# Esquem_tico.net
KiCad netlist of a schematic drawn in EAGLE
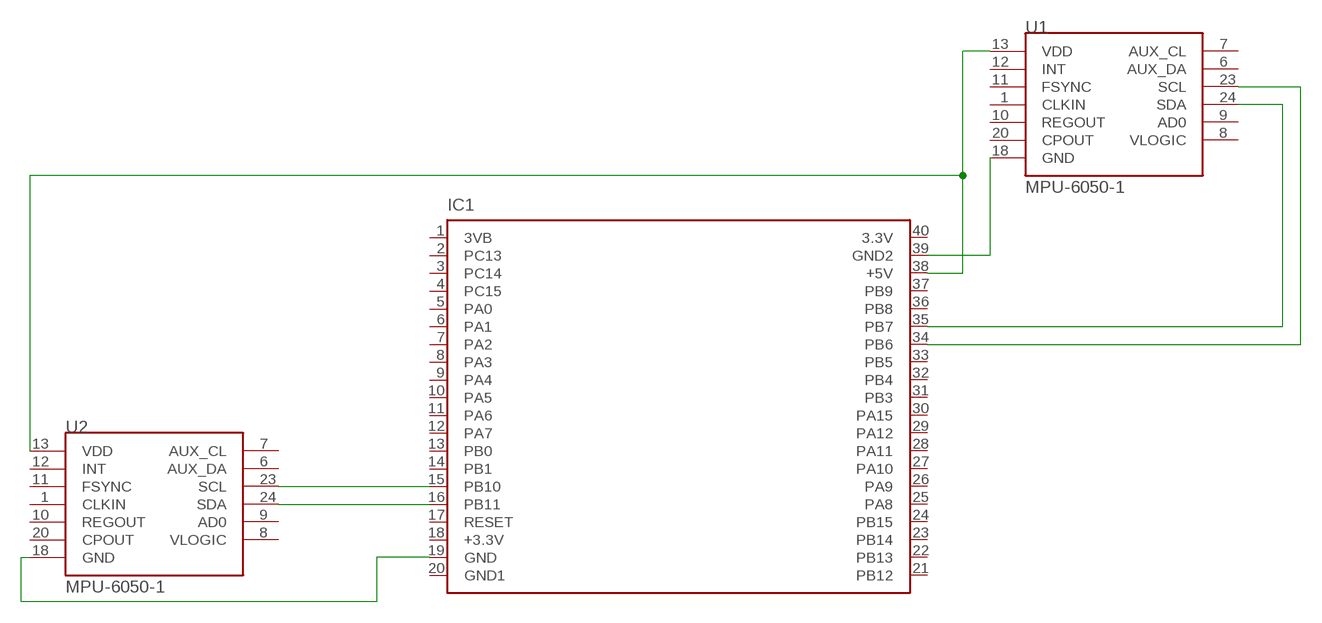
[diagram p0: schematic, sheet 1]

(export (version "E")
  (design (tool "Eeschema 10.0.6"))
  (components
    (comp (ref "IC1")
      (value "BLUEPILL550")
      (footprint "eagle-import:DIL40")
      (fields (field (name "MF") "BluePill"))
      (libsource (lib "eagle-import") (part "BLUEPILL550"))
    )
    (comp (ref "U1")
      (value "MPU-6050-1")
      (footprint "eagle-import:QFN-24-4MM2")
      (libsource (lib "eagle-import") (part "MPU-6050-1"))
    )
    (comp (ref "U2")
      (value "MPU-6050-1")
      (footprint "eagle-import:QFN-24-4MM2")
      (libsource (lib "eagle-import") (part "MPU-6050-1"))
    )
  )
  (nets
    (net (code "1") (name "/PA6") (class "Default")
      (node (ref "IC1") (pin "11") (pinfunction "PA6_11") (pintype "power_in"))
    )
    (net (code "2") (name "/PA7") (class "Default")
      (node (ref "IC1") (pin "12") (pinfunction "PA7_12") (pintype "power_in"))
    )
    (net (code "3") (name "/PB3") (class "Default")
      (node (ref "IC1") (pin "31") (pinfunction "PB3_31") (pintype "power_in"))
    )
    (net (code "4") (name "/PB4") (class "Default")
      (node (ref "IC1") (pin "32") (pinfunction "PB4_32") (pintype "power_in"))
    )
    (net (code "5") (name "Net-(IC1-+5V)") (class "Default")
      (node (ref "IC1") (pin "38") (pinfunction "+5V_38") (pintype "bidirectional"))
      (node (ref "U1") (pin "13") (pinfunction "VDD_13") (pintype "bidirectional"))
      (node (ref "U2") (pin "13") (pinfunction "VDD_13") (pintype "bidirectional"))
    )
    (net (code "6") (name "Net-(IC1-GND)") (class "Default")
      (node (ref "IC1") (pin "19") (pinfunction "GND_19") (pintype "bidirectional"))
      (node (ref "U2") (pin "18") (pinfunction "GND_18") (pintype "bidirectional"))
    )
    (net (code "7") (name "Net-(IC1-GND2)") (class "Default")
      (node (ref "IC1") (pin "39") (pinfunction "GND2_39") (pintype "bidirectional"))
      (node (ref "U1") (pin "18") (pinfunction "GND_18") (pintype "bidirectional"))
    )
    (net (code "8") (name "Net-(IC1-PB6)") (class "Default")
      (node (ref "IC1") (pin "34") (pinfunction "PB6_34") (pintype "bidirectional"))
      (node (ref "U1") (pin "23") (pinfunction "SCL_23") (pintype "bidirectional"))
    )
    (net (code "9") (name "Net-(IC1-PB7)") (class "Default")
      (node (ref "IC1") (pin "35") (pinfunction "PB7_35") (pintype "bidirectional"))
      (node (ref "U1") (pin "24") (pinfunction "SDA_24") (pintype "bidirectional"))
    )
    (net (code "10") (name "Net-(IC1-PB10)") (class "Default")
      (node (ref "IC1") (pin "15") (pinfunction "PB10_15") (pintype "bidirectional"))
      (node (ref "U2") (pin "23") (pinfunction "SCL_23") (pintype "bidirectional"))
    )
    (net (code "11") (name "Net-(IC1-PB11)") (class "Default")
      (node (ref "IC1") (pin "16") (pinfunction "PB11_16") (pintype "bidirectional"))
      (node (ref "U2") (pin "24") (pinfunction "SDA_24") (pintype "bidirectional"))
    )
    (net (code "12") (name "unconnected-(IC1-+3.3V-Pad18)") (class "Default")
      (node (ref "IC1") (pin "18") (pinfunction "+3.3V_18") (pintype "bidirectional"))
    )
    (net (code "13") (name "unconnected-(IC1-3.3V-Pad40)") (class "Default")
      (node (ref "IC1") (pin "40") (pinfunction "3.3V_40") (pintype "bidirectional"))
    )
    (net (code "14") (name "unconnected-(IC1-3VB-Pad1)") (class "Default")
      (node (ref "IC1") (pin "1") (pinfunction "3VB_1") (pintype "input"))
    )
    (net (code "15") (name "unconnected-(IC1-GND1-Pad20)") (class "Default")
      (node (ref "IC1") (pin "20") (pinfunction "GND1_20") (pintype "bidirectional"))
    )
    (net (code "16") (name "unconnected-(IC1-PA0-Pad5)") (class "Default")
      (node (ref "IC1") (pin "5") (pinfunction "PA0_5") (pintype "bidirectional"))
    )
    (net (code "17") (name "unconnected-(IC1-PA1-Pad6)") (class "Default")
      (node (ref "IC1") (pin "6") (pinfunction "PA1_6") (pintype "bidirectional"))
    )
    (net (code "18") (name "unconnected-(IC1-PA2-Pad7)") (class "Default")
      (node (ref "IC1") (pin "7") (pinfunction "PA2_7") (pintype "bidirectional"))
    )
    (net (code "19") (name "unconnected-(IC1-PA3-Pad8)") (class "Default")
      (node (ref "IC1") (pin "8") (pinfunction "PA3_8") (pintype "bidirectional"))
    )
    (net (code "20") (name "unconnected-(IC1-PA4-Pad9)") (class "Default")
      (node (ref "IC1") (pin "9") (pinfunction "PA4_9") (pintype "bidirectional"))
    )
    (net (code "21") (name "unconnected-(IC1-PA5-Pad10)") (class "Default")
      (node (ref "IC1") (pin "10") (pinfunction "PA5_10") (pintype "bidirectional"))
    )
    (net (code "22") (name "unconnected-(IC1-PA8-Pad25)") (class "Default")
      (node (ref "IC1") (pin "25") (pinfunction "PA8_25") (pintype "bidirectional"))
    )
    (net (code "23") (name "unconnected-(IC1-PA9-Pad26)") (class "Default")
      (node (ref "IC1") (pin "26") (pinfunction "PA9_26") (pintype "bidirectional"))
    )
    (net (code "24") (name "unconnected-(IC1-PA10-Pad27)") (class "Default")
      (node (ref "IC1") (pin "27") (pinfunction "PA10_27") (pintype "bidirectional"))
    )
    (net (code "25") (name "unconnected-(IC1-PA11-Pad28)") (class "Default")
      (node (ref "IC1") (pin "28") (pinfunction "PA11_28") (pintype "bidirectional"))
    )
    (net (code "26") (name "unconnected-(IC1-PA12-Pad29)") (class "Default")
      (node (ref "IC1") (pin "29") (pinfunction "PA12_29") (pintype "bidirectional"))
    )
    (net (code "27") (name "unconnected-(IC1-PA15-Pad30)") (class "Default")
      (node (ref "IC1") (pin "30") (pinfunction "PA15_30") (pintype "bidirectional"))
    )
    (net (code "28") (name "unconnected-(IC1-PB0-Pad13)") (class "Default")
      (node (ref "IC1") (pin "13") (pinfunction "PB0_13") (pintype "input"))
    )
    (net (code "29") (name "unconnected-(IC1-PB1-Pad14)") (class "Default")
      (node (ref "IC1") (pin "14") (pinfunction "PB1_14") (pintype "output"))
    )
    (net (code "30") (name "unconnected-(IC1-PB5-Pad33)") (class "Default")
      (node (ref "IC1") (pin "33") (pinfunction "PB5_33") (pintype "bidirectional"))
    )
    (net (code "31") (name "unconnected-(IC1-PB8-Pad36)") (class "Default")
      (node (ref "IC1") (pin "36") (pinfunction "PB8_36") (pintype "bidirectional"))
    )
    (net (code "32") (name "unconnected-(IC1-PB9-Pad37)") (class "Default")
      (node (ref "IC1") (pin "37") (pinfunction "PB9_37") (pintype "bidirectional"))
    )
    (net (code "33") (name "unconnected-(IC1-PB12-Pad21)") (class "Default")
      (node (ref "IC1") (pin "21") (pinfunction "PB12_21") (pintype "bidirectional"))
    )
    (net (code "34") (name "unconnected-(IC1-PB13-Pad22)") (class "Default")
      (node (ref "IC1") (pin "22") (pinfunction "PB13_22") (pintype "bidirectional"))
    )
    (net (code "35") (name "unconnected-(IC1-PB14-Pad23)") (class "Default")
      (node (ref "IC1") (pin "23") (pinfunction "PB14_23") (pintype "bidirectional"))
    )
    (net (code "36") (name "unconnected-(IC1-PB15-Pad24)") (class "Default")
      (node (ref "IC1") (pin "24") (pinfunction "PB15_24") (pintype "bidirectional"))
    )
    (net (code "37") (name "unconnected-(IC1-PC13-Pad2)") (class "Default")
      (node (ref "IC1") (pin "2") (pinfunction "PC13_2") (pintype "bidirectional"))
    )
    (net (code "38") (name "unconnected-(IC1-PC14-Pad3)") (class "Default")
      (node (ref "IC1") (pin "3") (pinfunction "PC14_3") (pintype "bidirectional"))
    )
    (net (code "39") (name "unconnected-(IC1-PC15-Pad4)") (class "Default")
      (node (ref "IC1") (pin "4") (pinfunction "PC15_4") (pintype "bidirectional"))
    )
    (net (code "40") (name "unconnected-(IC1-RESET-Pad17)") (class "Default")
      (node (ref "IC1") (pin "17") (pinfunction "RESET_17") (pintype "bidirectional"))
    )
    (net (code "41") (name "unconnected-(U1-AD0-Pad9)") (class "Default")
      (node (ref "U1") (pin "9") (pinfunction "AD0_9") (pintype "bidirectional"))
    )
    (net (code "42") (name "unconnected-(U1-AUX_CL-Pad7)") (class "Default")
      (node (ref "U1") (pin "7") (pinfunction "AUX_CL_7") (pintype "bidirectional"))
    )
    (net (code "43") (name "unconnected-(U1-AUX_DA-Pad6)") (class "Default")
      (node (ref "U1") (pin "6") (pinfunction "AUX_DA_6") (pintype "bidirectional"))
    )
    (net (code "44") (name "unconnected-(U1-CLKIN-Pad1)") (class "Default")
      (node (ref "U1") (pin "1") (pinfunction "CLKIN_1") (pintype "bidirectional"))
    )
    (net (code "45") (name "unconnected-(U1-CPOUT-Pad20)") (class "Default")
      (node (ref "U1") (pin "20") (pinfunction "CPOUT_20") (pintype "bidirectional"))
    )
    (net (code "46") (name "unconnected-(U1-FSYNC-Pad11)") (class "Default")
      (node (ref "U1") (pin "11") (pinfunction "FSYNC_11") (pintype "bidirectional"))
    )
    (net (code "47") (name "unconnected-(U1-INT-Pad12)") (class "Default")
      (node (ref "U1") (pin "12") (pinfunction "INT_12") (pintype "bidirectional"))
    )
    (net (code "48") (name "unconnected-(U1-REGOUT-Pad10)") (class "Default")
      (node (ref "U1") (pin "10") (pinfunction "REGOUT_10") (pintype "bidirectional"))
    )
    (net (code "49") (name "unconnected-(U1-VLOGIC-Pad8)") (class "Default")
      (node (ref "U1") (pin "8") (pinfunction "VLOGIC_8") (pintype "bidirectional"))
    )
    (net (code "50") (name "unconnected-(U2-AD0-Pad9)") (class "Default")
      (node (ref "U2") (pin "9") (pinfunction "AD0_9") (pintype "bidirectional"))
    )
    (net (code "51") (name "unconnected-(U2-AUX_CL-Pad7)") (class "Default")
      (node (ref "U2") (pin "7") (pinfunction "AUX_CL_7") (pintype "bidirectional"))
    )
    (net (code "52") (name "unconnected-(U2-AUX_DA-Pad6)") (class "Default")
      (node (ref "U2") (pin "6") (pinfunction "AUX_DA_6") (pintype "bidirectional"))
    )
    (net (code "53") (name "unconnected-(U2-CLKIN-Pad1)") (class "Default")
      (node (ref "U2") (pin "1") (pinfunction "CLKIN_1") (pintype "bidirectional"))
    )
    (net (code "54") (name "unconnected-(U2-CPOUT-Pad20)") (class "Default")
      (node (ref "U2") (pin "20") (pinfunction "CPOUT_20") (pintype "bidirectional"))
    )
    (net (code "55") (name "unconnected-(U2-FSYNC-Pad11)") (class "Default")
      (node (ref "U2") (pin "11") (pinfunction "FSYNC_11") (pintype "bidirectional"))
    )
    (net (code "56") (name "unconnected-(U2-INT-Pad12)") (class "Default")
      (node (ref "U2") (pin "12") (pinfunction "INT_12") (pintype "bidirectional"))
    )
    (net (code "57") (name "unconnected-(U2-REGOUT-Pad10)") (class "Default")
      (node (ref "U2") (pin "10") (pinfunction "REGOUT_10") (pintype "bidirectional"))
    )
    (net (code "58") (name "unconnected-(U2-VLOGIC-Pad8)") (class "Default")
      (node (ref "U2") (pin "8") (pinfunction "VLOGIC_8") (pintype "bidirectional"))
    )
  )
)
